# buoys_sch_v2.net
KiCad netlist of a schematic drawn in Altium Designer
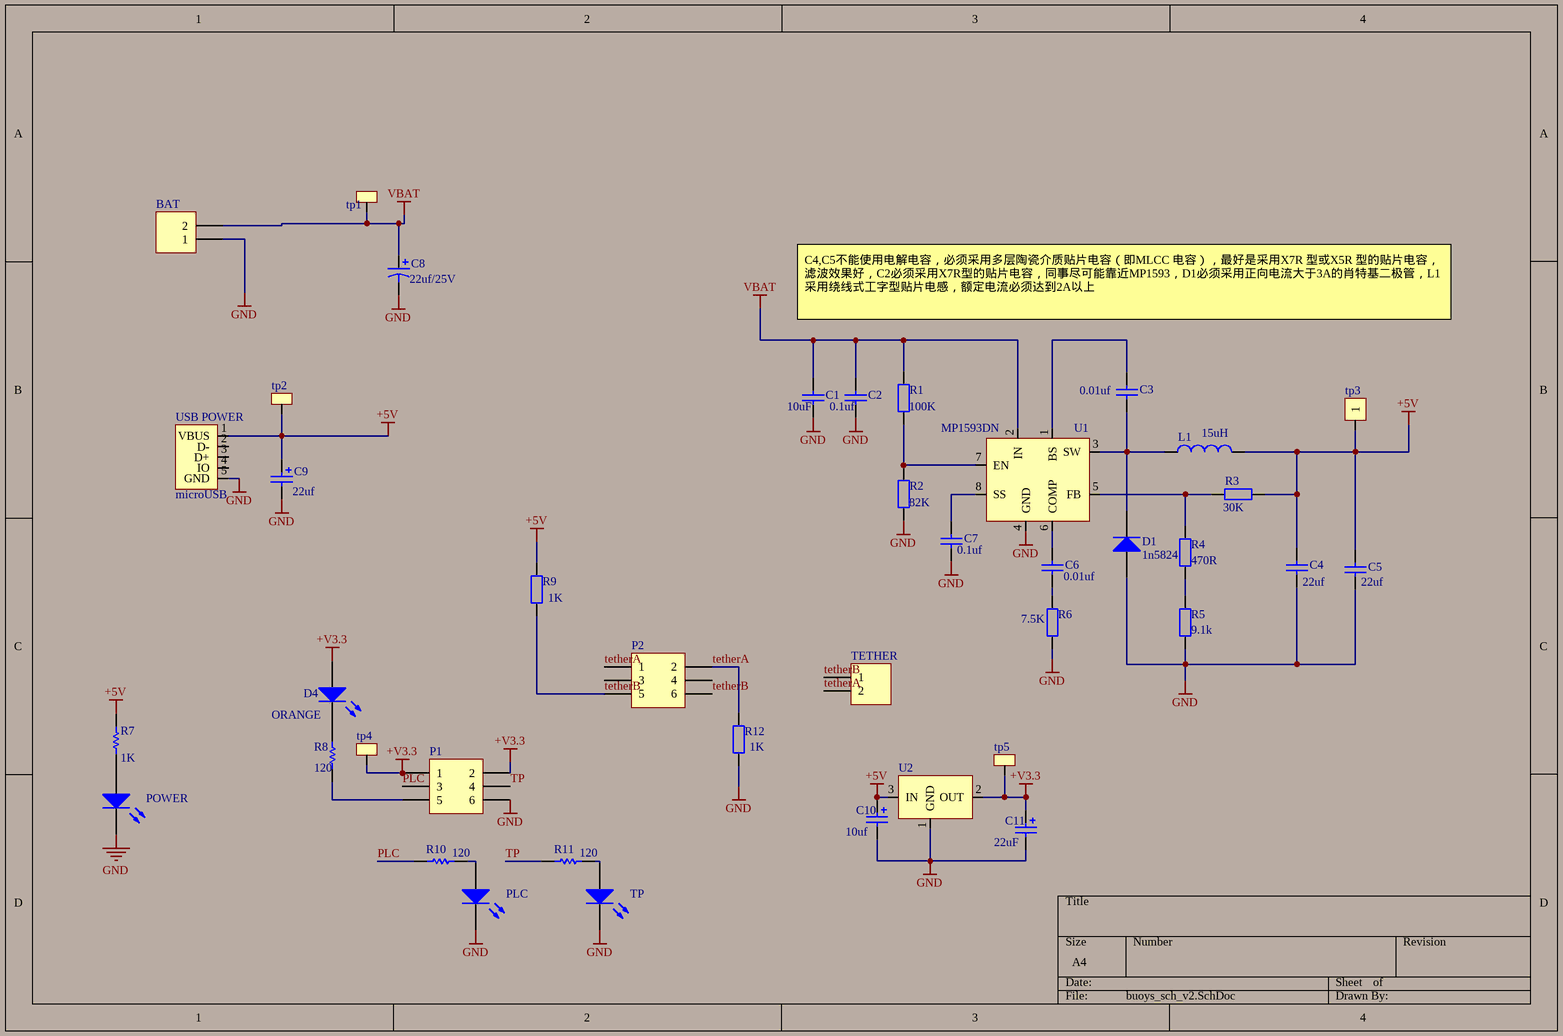
[diagram p0: buoys_sch_v2.SchDoc]

(export (version "E")
  (design (tool "Eeschema 10.0.6"))
  (components
    (comp (ref "BAT")
      (value "Header 2")
      (footprint "ConnectorBlue")
      (description "Header, 2-Pin")
      (fields (field (name "PUBLISHER") "Altium Limited"))
      (libsource (lib "Miscellaneous Connectors") (part "Header 2"))
    )
    (comp (ref "C1")
      (value "10uF")
      (footprint "C1206")
      (description "Capacitor")
      (fields (field (name "Comment") "Cap") (field (name "PUBLISHER") "Altium Limited"))
      (libsource (lib "Miscellaneous Devices") (part "Cap"))
    )
    (comp (ref "C2")
      (value "0.1uf")
      (footprint "6-0805_M")
      (description "Capacitor")
      (fields (field (name "Comment") "Cap") (field (name "PUBLISHER") "Altium Limited"))
      (libsource (lib "Miscellaneous Devices") (part "Cap"))
    )
    (comp (ref "C3")
      (value "0.01uf")
      (footprint "0603")
      (description "Capacitor")
      (fields (field (name "Comment") "Cap") (field (name "PUBLISHER") "Altium Limited"))
      (libsource (lib "Miscellaneous Devices") (part "Cap"))
    )
    (comp (ref "C4")
      (value "22uf")
      (footprint "C1206")
      (description "Capacitor")
      (fields (field (name "Comment") "Cap") (field (name "PUBLISHER") "Altium Limited"))
      (libsource (lib "Miscellaneous Devices") (part "Cap"))
    )
    (comp (ref "C5")
      (value "22uf")
      (footprint "C1206")
      (description "Capacitor")
      (fields (field (name "Comment") "Cap") (field (name "PUBLISHER") "Altium Limited"))
      (libsource (lib "Miscellaneous Devices") (part "Cap"))
    )
    (comp (ref "C6")
      (value "0.01uf")
      (footprint "0603")
      (description "Capacitor")
      (fields (field (name "Comment") "Cap") (field (name "PUBLISHER") "Altium Limited"))
      (libsource (lib "Miscellaneous Devices") (part "Cap"))
    )
    (comp (ref "C7")
      (value "0.1uf")
      (footprint "6-0805_M")
      (description "Capacitor")
      (fields (field (name "Comment") "Cap") (field (name "PUBLISHER") "Altium Limited"))
      (libsource (lib "Miscellaneous Devices") (part "Cap"))
    )
    (comp (ref "C8")
      (value "22uf/25V")
      (footprint "220UF-35V")
      (description "Polarized Capacitor (Radial)")
      (fields (field (name "Comment") "Cap Pol1") (field (name "PUBLISHER") "Altium Limited"))
      (libsource (lib "Miscellaneous Devices") (part "Cap Pol1"))
    )
    (comp (ref "C9")
      (value "22uf")
      (footprint "C1206")
      (description "Polarized Capacitor (Axial)")
      (fields (field (name "Comment") "Cap Pol2") (field (name "PUBLISHER") "Altium Limited"))
      (libsource (lib "Miscellaneous Devices") (part "Cap Pol2"))
    )
    (comp (ref "C10")
      (value "10uf")
      (footprint "1206")
      (description "Polarized Capacitor (Axial)")
      (fields (field (name "Comment") "Cap Pol2") (field (name "PUBLISHER") "Altium Limited"))
      (libsource (lib "Miscellaneous Devices") (part "Cap Pol2"))
    )
    (comp (ref "C11")
      (value "22uF")
      (footprint "0603")
      (description "Polarized Capacitor (Axial)")
      (fields (field (name "Comment") "Cap Pol2") (field (name "PUBLISHER") "Altium Limited"))
      (libsource (lib "Miscellaneous Devices") (part "Cap Pol2"))
    )
    (comp (ref "D1")
      (value "1n5824")
      (footprint "1n5824_1")
      (description "Default Diode")
      (fields (field (name "PUBLISHER") "Altium Limited"))
      (libsource (lib "Miscellaneous Devices") (part "Diode"))
    )
    (comp (ref "D4")
      (value "ORANGE")
      (footprint "6-0805_M")
      (description "Typical RED, GREEN, YELLOW, AMBER GaAs LED")
      (fields (field (name "PUBLISHER") "Altium Limited"))
      (libsource (lib "Miscellaneous Devices") (part "LED2"))
    )
    (comp (ref "L1")
      (value "15uH")
      (footprint "0630")
      (description "Inductor")
      (fields (field (name "PUBLISHER") "Altium Limited"))
      (libsource (lib "Miscellaneous Devices") (part "Inductor"))
    )
    (comp (ref "P1")
      (value "Header 3X2")
      (footprint "HDR2X3")
      (description "Header, 3-Pin, Dual row")
      (fields (field (name "PUBLISHER") "Altium Limited"))
      (libsource (lib "Miscellaneous Connectors") (part "Header 3X2"))
    )
    (comp (ref "P2")
      (value "Header 3X2")
      (footprint "HDR2X3")
      (description "Header, 3-Pin, Dual row")
      (fields (field (name "PUBLISHER") "Altium Limited"))
      (libsource (lib "Miscellaneous Connectors") (part "Header 3X2"))
    )
    (comp (ref "PLC")
      (value "RED")
      (footprint "6-0805_M")
      (description "Typical RED, GREEN, YELLOW, AMBER GaAs LED")
      (fields (field (name "PUBLISHER") "Altium Limited"))
      (libsource (lib "Miscellaneous Devices") (part "LED2"))
    )
    (comp (ref "POWER")
      (value "RED POWER")
      (footprint "6-0805_M")
      (description "Typical RED, GREEN, YELLOW, AMBER GaAs LED")
      (fields (field (name "PUBLISHER") "Altium Limited"))
      (libsource (lib "Miscellaneous Devices") (part "LED2"))
    )
    (comp (ref "R1")
      (value "100K")
      (footprint "6-0805_M")
      (description "Resistor")
      (fields (field (name "Comment") "Res2") (field (name "PUBLISHER") "Altium Limited"))
      (libsource (lib "Miscellaneous Devices") (part "Res2"))
    )
    (comp (ref "R2")
      (value "82K")
      (footprint "6-0805_M")
      (description "Resistor")
      (fields (field (name "Comment") "Res2") (field (name "PUBLISHER") "Altium Limited"))
      (libsource (lib "Miscellaneous Devices") (part "Res2"))
    )
    (comp (ref "R3")
      (value "30K")
      (footprint "6-0805_M")
      (description "Resistor")
      (fields (field (name "Comment") "Res2") (field (name "PUBLISHER") "Altium Limited"))
      (libsource (lib "") (part "Res2_1"))
    )
    (comp (ref "R4")
      (value "470R")
      (footprint "6-0805_M")
      (description "Resistor")
      (fields (field (name "Comment") "Res2") (field (name "PUBLISHER") "Altium Limited"))
      (libsource (lib "Miscellaneous Devices") (part "Res2"))
    )
    (comp (ref "R5")
      (value "9.1k")
      (footprint "6-0805_M")
      (description "Resistor")
      (fields (field (name "Comment") "Res2") (field (name "PUBLISHER") "Altium Limited"))
      (libsource (lib "Miscellaneous Devices") (part "Res2"))
    )
    (comp (ref "R6")
      (value "7.5K")
      (footprint "6-0805_M")
      (description "Resistor")
      (fields (field (name "Comment") "Res2") (field (name "PUBLISHER") "Altium Limited"))
      (libsource (lib "Miscellaneous Devices") (part "Res2"))
    )
    (comp (ref "R7")
      (value "1K")
      (footprint "6-0805_M")
      (description "Resistor")
      (fields (field (name "Comment") "Res1") (field (name "PUBLISHER") "Altium Limited"))
      (libsource (lib "Miscellaneous Devices") (part "Res1"))
    )
    (comp (ref "R8")
      (value "120")
      (footprint "6-0805_L")
      (description "Resistor")
      (fields (field (name "Comment") "Res1") (field (name "PUBLISHER") "Altium Limited"))
      (libsource (lib "Miscellaneous Devices") (part "Res1"))
    )
    (comp (ref "R9")
      (value "1K")
      (footprint "6-0805_M")
      (description "Resistor")
      (fields (field (name "Comment") "Res2") (field (name "PUBLISHER") "Altium Limited"))
      (libsource (lib "Miscellaneous Devices") (part "Res2"))
    )
    (comp (ref "R10")
      (value "120")
      (footprint "6-0805_L")
      (description "Resistor")
      (fields (field (name "Comment") "Res1") (field (name "PUBLISHER") "Altium Limited"))
      (libsource (lib "Miscellaneous Devices") (part "Res1"))
    )
    (comp (ref "R11")
      (value "120")
      (footprint "6-0805_L")
      (description "Resistor")
      (fields (field (name "Comment") "Res1") (field (name "PUBLISHER") "Altium Limited"))
      (libsource (lib "Miscellaneous Devices") (part "Res1"))
    )
    (comp (ref "R12")
      (value "1K")
      (footprint "6-0805_M")
      (description "Resistor")
      (fields (field (name "Comment") "Res2") (field (name "PUBLISHER") "Altium Limited"))
      (libsource (lib "Miscellaneous Devices") (part "Res2"))
    )
    (comp (ref "TETHER")
      (value "Header 2")
      (footprint "ConnectorBlue")
      (description "Header, 2-Pin")
      (fields (field (name "PUBLISHER") "Altium Limited"))
      (libsource (lib "") (part "Header 2_1"))
    )
    (comp (ref "TP")
      (value "BLUE")
      (footprint "6-0805_M")
      (description "Typical RED, GREEN, YELLOW, AMBER GaAs LED")
      (fields (field (name "PUBLISHER") "Altium Limited"))
      (libsource (lib "Miscellaneous Devices") (part "LED2"))
    )
    (comp (ref "tp1")
      (value "testpoint")
      (footprint "tp")
      (libsource (lib "buoys_sch_lib") (part "testpoint"))
    )
    (comp (ref "tp2")
      (value "testpoint")
      (footprint "tp")
      (libsource (lib "buoys_sch_lib") (part "testpoint"))
    )
    (comp (ref "tp3") (value "tp") (footprint "testpoint") (libsource (lib "power2pix_sch_lib") (part "tp")))
    (comp (ref "tp4")
      (value "testpoint")
      (footprint "tp")
      (libsource (lib "buoys_sch_lib") (part "testpoint"))
    )
    (comp (ref "tp5")
      (value "testpoint")
      (footprint "tp")
      (libsource (lib "buoys_sch_lib") (part "testpoint"))
    )
    (comp (ref "U1")
      (value "MP1593DN")
      (footprint "SO8_M")
      (libsource (lib "power2pix_sch_lib") (part "MP1593DN"))
    )
    (comp (ref "U2")
      (value "AMS1117-3.3")
      (footprint "SOT223_M")
      (libsource (lib "buoys_sch_lib") (part "Component_3"))
    )
    (comp (ref "USB POWER")
      (value "microUSB")
      (footprint "microUSB")
      (libsource (lib "buoys_sch_lib") (part "Component_1"))
    )
  )
  (nets
    (net (code "1") (name "+5V") (class "Default")
      (node (ref "C10") (pin "1") (pinfunction "1_1") (pintype "passive"))
      (node (ref "C4") (pin "2") (pinfunction "2_2") (pintype "passive"))
      (node (ref "C5") (pin "2") (pinfunction "2_2") (pintype "passive"))
      (node (ref "C9") (pin "1") (pinfunction "1_1") (pintype "passive"))
      (node (ref "L1") (pin "2") (pinfunction "2_2") (pintype "passive"))
      (node (ref "R3") (pin "1") (pinfunction "1_1") (pintype "passive"))
      (node (ref "R7") (pin "2") (pinfunction "2_2") (pintype "passive"))
      (node (ref "R9") (pin "2") (pinfunction "2_2") (pintype "passive"))
      (node (ref "U2") (pin "3") (pinfunction "IN_3") (pintype "passive"))
      (node (ref "USB POWER") (pin "1") (pinfunction "VBUS_1") (pintype "power_in"))
      (node (ref "tp2") (pin "1") (pinfunction "TP_1") (pintype "passive"))
      (node (ref "tp3") (pin "1") (pinfunction "1_1") (pintype "passive"))
    )
    (net (code "2") (name "+V3.3") (class "Default")
      (node (ref "C11") (pin "1") (pinfunction "1_1") (pintype "passive"))
      (node (ref "D4") (pin "1") (pinfunction "A_1") (pintype "passive"))
      (node (ref "P1") (pin "1") (pinfunction "1_1") (pintype "passive"))
      (node (ref "P1") (pin "2") (pinfunction "2_2") (pintype "passive"))
      (node (ref "U2") (pin "2") (pinfunction "OUT_2") (pintype "passive"))
      (node (ref "tp4") (pin "1") (pinfunction "TP_1") (pintype "passive"))
      (node (ref "tp5") (pin "1") (pinfunction "TP_1") (pintype "passive"))
    )
    (net (code "3") (name "/PLC") (class "Default")
      (node (ref "P1") (pin "3") (pinfunction "3_3") (pintype "passive"))
      (node (ref "R10") (pin "2") (pinfunction "2_2") (pintype "passive"))
    )
    (net (code "4") (name "/TP") (class "Default")
      (node (ref "P1") (pin "4") (pinfunction "4_4") (pintype "passive"))
      (node (ref "R11") (pin "2") (pinfunction "2_2") (pintype "passive"))
    )
    (net (code "5") (name "/tetherA") (class "Default")
      (node (ref "P2") (pin "1") (pinfunction "1_1") (pintype "passive"))
      (node (ref "P2") (pin "2") (pinfunction "2_2") (pintype "passive"))
      (node (ref "R12") (pin "2") (pinfunction "2_2") (pintype "passive"))
      (node (ref "TETHER") (pin "2") (pinfunction "2_2") (pintype "passive"))
    )
    (net (code "6") (name "/tetherB") (class "Default")
      (node (ref "P2") (pin "5") (pinfunction "5_5") (pintype "passive"))
      (node (ref "P2") (pin "6") (pinfunction "6_6") (pintype "passive"))
      (node (ref "R9") (pin "1") (pinfunction "1_1") (pintype "passive"))
      (node (ref "TETHER") (pin "1") (pinfunction "1_1") (pintype "passive"))
    )
    (net (code "7") (name "GND") (class "Default")
      (node (ref "BAT") (pin "1") (pinfunction "1_1") (pintype "passive"))
      (node (ref "C1") (pin "1") (pinfunction "1_1") (pintype "passive"))
      (node (ref "C10") (pin "2") (pinfunction "2_2") (pintype "passive"))
      (node (ref "C11") (pin "2") (pinfunction "2_2") (pintype "passive"))
      (node (ref "C2") (pin "1") (pinfunction "1_1") (pintype "passive"))
      (node (ref "C4") (pin "1") (pinfunction "1_1") (pintype "passive"))
      (node (ref "C5") (pin "1") (pinfunction "1_1") (pintype "passive"))
      (node (ref "C7") (pin "1") (pinfunction "1_1") (pintype "passive"))
      (node (ref "C8") (pin "2") (pinfunction "2_2") (pintype "passive"))
      (node (ref "C9") (pin "2") (pinfunction "2_2") (pintype "passive"))
      (node (ref "D1") (pin "1") (pinfunction "A_1") (pintype "passive"))
      (node (ref "P1") (pin "6") (pinfunction "6_6") (pintype "passive"))
      (node (ref "PLC") (pin "2") (pinfunction "K_2") (pintype "passive"))
      (node (ref "POWER") (pin "2") (pinfunction "K_2") (pintype "passive"))
      (node (ref "R12") (pin "1") (pinfunction "1_1") (pintype "passive"))
      (node (ref "R2") (pin "1") (pinfunction "1_1") (pintype "passive"))
      (node (ref "R5") (pin "1") (pinfunction "1_1") (pintype "passive"))
      (node (ref "R6") (pin "1") (pinfunction "1_1") (pintype "passive"))
      (node (ref "TP") (pin "2") (pinfunction "K_2") (pintype "passive"))
      (node (ref "U1") (pin "4") (pinfunction "GND_4") (pintype "passive"))
      (node (ref "U2") (pin "1") (pinfunction "GND_1") (pintype "passive"))
      (node (ref "USB POWER") (pin "5") (pinfunction "GND_5") (pintype "power_in"))
    )
    (net (code "8") (name "Net-(C6-Pad1)") (class "Default")
      (node (ref "C6") (pin "1") (pinfunction "1_1") (pintype "passive"))
      (node (ref "R6") (pin "2") (pinfunction "2_2") (pintype "passive"))
    )
    (net (code "9") (name "Net-(D1-K)") (class "Default")
      (node (ref "C3") (pin "1") (pinfunction "1_1") (pintype "passive"))
      (node (ref "D1") (pin "2") (pinfunction "K_2") (pintype "passive"))
      (node (ref "L1") (pin "1") (pinfunction "1_1") (pintype "passive"))
      (node (ref "U1") (pin "3") (pinfunction "SW_3") (pintype "passive"))
    )
    (net (code "10") (name "Net-(D4-K)") (class "Default")
      (node (ref "D4") (pin "2") (pinfunction "K_2") (pintype "passive"))
      (node (ref "R8") (pin "1") (pinfunction "1_1") (pintype "passive"))
    )
    (net (code "11") (name "Net-(P1-Pad5)") (class "Default")
      (node (ref "P1") (pin "5") (pinfunction "5_5") (pintype "passive"))
      (node (ref "R8") (pin "2") (pinfunction "2_2") (pintype "passive"))
    )
    (net (code "12") (name "Net-(PLC-A)") (class "Default")
      (node (ref "PLC") (pin "1") (pinfunction "A_1") (pintype "passive"))
      (node (ref "R10") (pin "1") (pinfunction "1_1") (pintype "passive"))
    )
    (net (code "13") (name "Net-(POWER-A)") (class "Default")
      (node (ref "POWER") (pin "1") (pinfunction "A_1") (pintype "passive"))
      (node (ref "R7") (pin "1") (pinfunction "1_1") (pintype "passive"))
    )
    (net (code "14") (name "Net-(R4-Pad1)") (class "Default")
      (node (ref "R4") (pin "1") (pinfunction "1_1") (pintype "passive"))
      (node (ref "R5") (pin "2") (pinfunction "2_2") (pintype "passive"))
    )
    (net (code "15") (name "Net-(TP-A)") (class "Default")
      (node (ref "R11") (pin "1") (pinfunction "1_1") (pintype "passive"))
      (node (ref "TP") (pin "1") (pinfunction "A_1") (pintype "passive"))
    )
    (net (code "16") (name "Net-(U1-BS)") (class "Default")
      (node (ref "C3") (pin "2") (pinfunction "2_2") (pintype "passive"))
      (node (ref "U1") (pin "1") (pinfunction "BS_1") (pintype "passive"))
    )
    (net (code "17") (name "Net-(U1-COMP)") (class "Default")
      (node (ref "C6") (pin "2") (pinfunction "2_2") (pintype "passive"))
      (node (ref "U1") (pin "6") (pinfunction "COMP_6") (pintype "passive"))
    )
    (net (code "18") (name "Net-(U1-EN)") (class "Default")
      (node (ref "R1") (pin "1") (pinfunction "1_1") (pintype "passive"))
      (node (ref "R2") (pin "2") (pinfunction "2_2") (pintype "passive"))
      (node (ref "U1") (pin "7") (pinfunction "EN_7") (pintype "passive"))
    )
    (net (code "19") (name "Net-(U1-FB)") (class "Default")
      (node (ref "R3") (pin "2") (pinfunction "2_2") (pintype "passive"))
      (node (ref "R4") (pin "2") (pinfunction "2_2") (pintype "passive"))
      (node (ref "U1") (pin "5") (pinfunction "FB_5") (pintype "passive"))
    )
    (net (code "20") (name "Net-(U1-SS)") (class "Default")
      (node (ref "C7") (pin "2") (pinfunction "2_2") (pintype "passive"))
      (node (ref "U1") (pin "8") (pinfunction "SS_8") (pintype "passive"))
    )
    (net (code "21") (name "VBAT") (class "Default")
      (node (ref "BAT") (pin "2") (pinfunction "2_2") (pintype "passive"))
      (node (ref "C1") (pin "2") (pinfunction "2_2") (pintype "passive"))
      (node (ref "C2") (pin "2") (pinfunction "2_2") (pintype "passive"))
      (node (ref "C8") (pin "1") (pinfunction "1_1") (pintype "passive"))
      (node (ref "R1") (pin "2") (pinfunction "2_2") (pintype "passive"))
      (node (ref "U1") (pin "2") (pinfunction "IN_2") (pintype "passive"))
      (node (ref "tp1") (pin "1") (pinfunction "TP_1") (pintype "passive"))
    )
    (net (code "22") (name "unconnected-(P2-Pad3)") (class "Default")
      (node (ref "P2") (pin "3") (pinfunction "3_3") (pintype "passive"))
    )
    (net (code "23") (name "unconnected-(P2-Pad4)") (class "Default")
      (node (ref "P2") (pin "4") (pinfunction "4_4") (pintype "passive"))
    )
    (net (code "24") (name "unconnected-(USB POWER-D+-Pad3)") (class "Default")
      (node (ref "USB POWER") (pin "3") (pinfunction "D+_3") (pintype "passive"))
    )
    (net (code "25") (name "unconnected-(USB POWER-D--Pad2)") (class "Default")
      (node (ref "USB POWER") (pin "2") (pinfunction "D-_2") (pintype "passive"))
    )
    (net (code "26") (name "unconnected-(USB POWER-IO-Pad4)") (class "Default")
      (node (ref "USB POWER") (pin "4") (pinfunction "IO_4") (pintype "passive"))
    )
  )
)
